# Mini_RGB.net
KiCad netlist of a schematic drawn in EAGLE
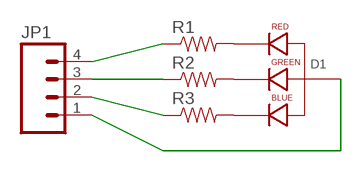
[diagram p0: schematic, sheet 1]

(export (version "E")
  (design (tool "Eeschema 10.0.6"))
  (components
    (comp (ref "D1")
      (value "LED-RGB-CA-THRUDIFFUSE")
      (footprint "eagle-import:LED-RGB-THRU")
      (libsource (lib "eagle-import") (part "LED-RGB-CA-THRUDIFFUSE"))
    )
    (comp (ref "JP1")
      (value "M04PTH")
      (footprint "eagle-import:1X04")
      (libsource (lib "eagle-import") (part "M04PTH"))
    )
    (comp (ref "R1")
      (value "RESISTORAXIAL-0.3")
      (footprint "eagle-import:AXIAL-0.3")
      (libsource (lib "eagle-import") (part "RESISTORAXIAL-0.3"))
    )
    (comp (ref "R2")
      (value "RESISTORAXIAL-0.3")
      (footprint "eagle-import:AXIAL-0.3")
      (libsource (lib "eagle-import") (part "RESISTORAXIAL-0.3"))
    )
    (comp (ref "R3")
      (value "RESISTORAXIAL-0.3")
      (footprint "eagle-import:AXIAL-0.3")
      (libsource (lib "eagle-import") (part "RESISTORAXIAL-0.3"))
    )
  )
  (nets
    (net (code "1") (name "Net-(D1-ANODE)") (class "Default")
      (node (ref "D1") (pin "2") (pinfunction "ANODE_2") (pintype "bidirectional"))
      (node (ref "JP1") (pin "1") (pinfunction "1_1") (pintype "passive"))
    )
    (net (code "2") (name "Net-(D1-BLUE_CATHODE)") (class "Default")
      (node (ref "D1") (pin "4") (pinfunction "BLUE_CATHODE_4") (pintype "bidirectional"))
      (node (ref "R3") (pin "P$2") (pinfunction "2_P$2") (pintype "passive"))
    )
    (net (code "3") (name "Net-(D1-GREEN_CATHODE)") (class "Default")
      (node (ref "D1") (pin "3") (pinfunction "GREEN_CATHODE_3") (pintype "bidirectional"))
      (node (ref "R2") (pin "P$2") (pinfunction "2_P$2") (pintype "passive"))
    )
    (net (code "4") (name "Net-(D1-RED_CATHODE)") (class "Default")
      (node (ref "D1") (pin "1") (pinfunction "RED_CATHODE_1") (pintype "bidirectional"))
      (node (ref "R1") (pin "P$2") (pinfunction "2_P$2") (pintype "passive"))
    )
    (net (code "5") (name "Net-(R1-1)") (class "Default")
      (node (ref "JP1") (pin "4") (pinfunction "4_4") (pintype "passive"))
      (node (ref "R1") (pin "P$1") (pinfunction "1_P$1") (pintype "passive"))
    )
    (net (code "6") (name "Net-(R2-1)") (class "Default")
      (node (ref "JP1") (pin "3") (pinfunction "3_3") (pintype "passive"))
      (node (ref "R2") (pin "P$1") (pinfunction "1_P$1") (pintype "passive"))
    )
    (net (code "7") (name "Net-(R3-1)") (class "Default")
      (node (ref "JP1") (pin "2") (pinfunction "2_2") (pintype "passive"))
      (node (ref "R3") (pin "P$1") (pinfunction "1_P$1") (pintype "passive"))
    )
  )
)
